# Positive_Pwr.net
KiCad netlist of a schematic drawn in Altium Designer
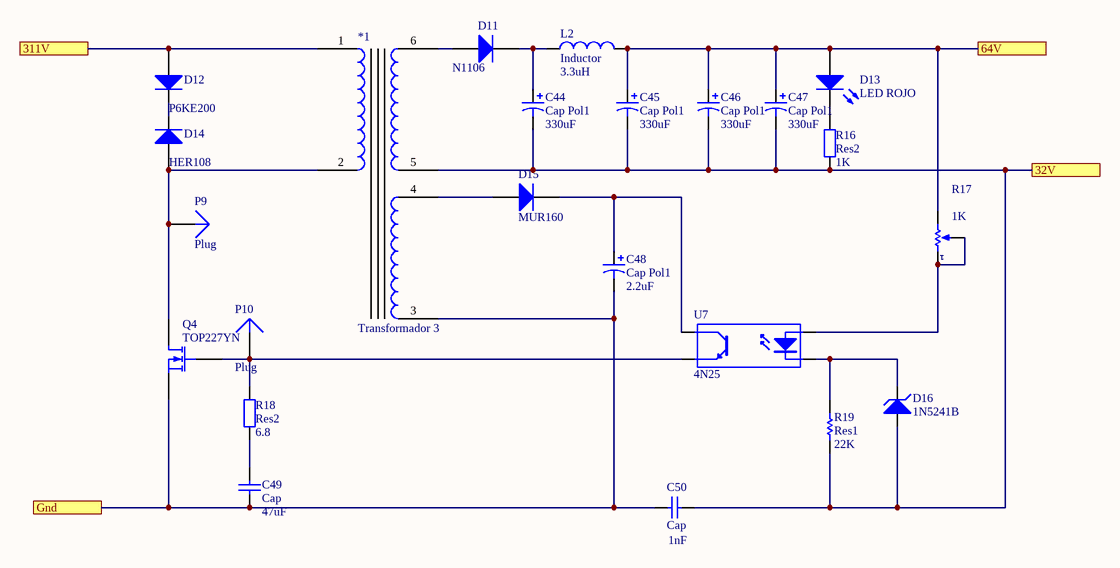
[diagram p0: Positive Pwr.SchDoc]

(export (version "E")
  (design (tool "Eeschema 10.0.6"))
  (components
    (comp (ref "*1")
      (value "Transformador 3")
      (footprint "Transformador_flyback - duplicate")
      (libsource (lib "Userlib") (part "Transformador 3"))
    )
    (comp (ref "C44")
      (value "Cap Pol1")
      (footprint "CAPR D500 H1200 R200 mil")
      (description "Polarized Capacitor (Radial)")
      (fields (field (name "ALTIUM_VALUE") "330uF") (field (name "PUBLISHER") "Altium Limited"))
      (libsource (lib "Miscellaneous Devices") (part "Cap Pol1"))
    )
    (comp (ref "C45")
      (value "Cap Pol1")
      (footprint "CAPR D500 H1200 R200 mil")
      (description "Polarized Capacitor (Radial)")
      (fields (field (name "ALTIUM_VALUE") "330uF") (field (name "PUBLISHER") "Altium Limited"))
      (libsource (lib "Miscellaneous Devices") (part "Cap Pol1"))
    )
    (comp (ref "C46")
      (value "Cap Pol1")
      (footprint "CAPR D500 H1200 R200 mil")
      (description "Polarized Capacitor (Radial)")
      (fields (field (name "ALTIUM_VALUE") "330uF") (field (name "PUBLISHER") "Altium Limited"))
      (libsource (lib "Miscellaneous Devices") (part "Cap Pol1"))
    )
    (comp (ref "C47")
      (value "Cap Pol1")
      (footprint "CAPR D500 H1200 R200 mil")
      (description "Polarized Capacitor (Radial)")
      (fields (field (name "ALTIUM_VALUE") "330uF") (field (name "PUBLISHER") "Altium Limited"))
      (libsource (lib "Miscellaneous Devices") (part "Cap Pol1"))
    )
    (comp (ref "C48")
      (value "Cap Pol1")
      (footprint "CAPR D200 H450 R100 mil")
      (description "Polarized Capacitor (Radial)")
      (fields (field (name "ALTIUM_VALUE") "2.2uF") (field (name "PUBLISHER") "Altium Limited"))
      (libsource (lib "Miscellaneous Devices") (part "Cap Pol1"))
    )
    (comp (ref "C49")
      (value "Cap")
      (footprint "CAPR D250 H450 R100 mil")
      (description "Capacitor")
      (fields (field (name "ALTIUM_VALUE") "47uF") (field (name "PUBLISHER") "Altium Limited"))
      (libsource (lib "Miscellaneous Devices") (part "Cap"))
    )
    (comp (ref "C50")
      (value "Cap")
      (footprint "RAD-0.2")
      (description "Capacitor")
      (fields (field (name "ALTIUM_VALUE") "1nF") (field (name "PUBLISHER") "Altium Limited"))
      (libsource (lib "Miscellaneous Devices") (part "Cap"))
    )
    (comp (ref "D11")
      (value "N1106")
      (footprint "TO-220_A")
      (description "High Conductance Fast Diode")
      (fields (field (name "PUBLISHER") "Altium Limited"))
      (libsource (lib "") (part "Diode 1N4148_1"))
    )
    (comp (ref "D12")
      (value "P6KE200")
      (footprint "DO-15")
      (description "High Conductance Fast Diode")
      (fields (field (name "PUBLISHER") "Altium Limited"))
      (libsource (lib "Miscellaneous Devices") (part "Diode 1N4148"))
    )
    (comp (ref "D13")
      (value "LED ROJO")
      (footprint "Led 5mm ROJO")
      (description "Typical INFRARED GaAs LED")
      (fields (field (name "PUBLISHER") "Altium Limited"))
      (libsource (lib "Miscellaneous Devices") (part "LED0"))
    )
    (comp (ref "D14")
      (value "HER108")
      (footprint "DO-41")
      (description "High Conductance Fast Diode")
      (fields (field (name "PUBLISHER") "Altium Limited"))
      (libsource (lib "Miscellaneous Devices") (part "Diode 1N4148"))
    )
    (comp (ref "D15")
      (value "MUR160")
      (footprint "DO-41")
      (description "High Conductance Fast Diode")
      (fields (field (name "PUBLISHER") "Altium Limited"))
      (libsource (lib "Miscellaneous Devices") (part "Diode 1N4148"))
    )
    (comp (ref "D16")
      (value "Diodo Zener")
      (footprint "DO-41")
      (fields (field (name "VALOR") "1N5241B"))
      (libsource (lib "RUF-Dispositivos-Grales") (part "Diodo Zener"))
    )
    (comp (ref "L2")
      (value "Inductor")
      (footprint "Bobina 1.5*3")
      (fields (field (name "ALTIUM_VALUE") "3.3uH") (field (name "PUBLISHER") "Altium Limited"))
      (libsource (lib "Miscellaneous Devices") (part "Inductor"))
    )
    (comp (ref "P9")
      (value "Plug")
      (footprint "PIN1")
      (fields (field (name "PUBLISHER") "Altium Limited"))
      (libsource (lib "Miscellaneous Connectors") (part "Plug"))
    )
    (comp (ref "P10")
      (value "Plug")
      (footprint "PIN1")
      (fields (field (name "PUBLISHER") "Altium Limited"))
      (libsource (lib "Miscellaneous Connectors") (part "Plug"))
    )
    (comp (ref "Q4")
      (value "TOP227YN")
      (footprint "TO-220AB")
      (description "N-Channel MOSFET")
      (fields (field (name "PUBLISHER") "Altium Limited"))
      (libsource (lib "Miscellaneous Devices") (part "MOSFET-N"))
    )
    (comp (ref "R16")
      (value "Res2")
      (footprint "1206 resistor")
      (description "Resistor")
      (fields (field (name "ALTIUM_VALUE") "1K") (field (name "PUBLISHER") "Altium Limited"))
      (libsource (lib "Miscellaneous Devices") (part "Res2"))
    )
    (comp (ref "R17")
      (value "Trimpot")
      (footprint "Trimpot Horizontal")
      (description "Preset")
      (fields (field (name "VALOR") "1K"))
      (libsource (lib "RUF-Dispositivos-Grales") (part "Trimpot"))
    )
    (comp (ref "R18")
      (value "Res2")
      (footprint "1206 resistor")
      (description "Resistor")
      (fields (field (name "ALTIUM_VALUE") "6.8") (field (name "PUBLISHER") "Altium Limited"))
      (libsource (lib "Miscellaneous Devices") (part "Res2"))
    )
    (comp (ref "R19")
      (value "Res1")
      (footprint "1206 resistor")
      (description "Resistor")
      (fields (field (name "ALTIUM_VALUE") "22K") (field (name "PUBLISHER") "Altium Limited"))
      (libsource (lib "Miscellaneous Devices") (part "Res1"))
    )
    (comp (ref "U7")
      (value "4N25")
      (footprint "DIP-4")
      (description "4-Pin Phototransistor Optocoupler")
      (fields (field (name "PUBLISHER") "Altium Limited"))
      (libsource (lib "Miscellaneous Devices") (part "Optoisolator1"))
    )
  )
  (nets
    (net (code "1") (name "/32V") (class "Default")
      (node (ref "*1") (pin "5") (pinfunction "L_5") (pintype "passive"))
      (node (ref "C44") (pin "2") (pinfunction "2_2") (pintype "passive"))
      (node (ref "C45") (pin "2") (pinfunction "2_2") (pintype "passive"))
      (node (ref "C46") (pin "2") (pinfunction "2_2") (pintype "passive"))
      (node (ref "C47") (pin "2") (pinfunction "2_2") (pintype "passive"))
      (node (ref "C50") (pin "2") (pinfunction "2_2") (pintype "passive"))
      (node (ref "D16") (pin "1") (pinfunction "A_1") (pintype "passive"))
      (node (ref "R16") (pin "1") (pinfunction "1_1") (pintype "passive"))
      (node (ref "R19") (pin "1") (pinfunction "1_1") (pintype "passive"))
    )
    (net (code "2") (name "/64V") (class "Default")
      (node (ref "C45") (pin "1") (pinfunction "1_1") (pintype "passive"))
      (node (ref "C46") (pin "1") (pinfunction "1_1") (pintype "passive"))
      (node (ref "C47") (pin "1") (pinfunction "1_1") (pintype "passive"))
      (node (ref "D13") (pin "1") (pinfunction "A_1") (pintype "passive"))
      (node (ref "L2") (pin "2") (pinfunction "2_2") (pintype "passive"))
      (node (ref "R17") (pin "2") (pinfunction "BOT_2") (pintype "passive"))
    )
    (net (code "3") (name "/311V") (class "Default")
      (node (ref "*1") (pin "1") (pinfunction "L_1") (pintype "passive"))
      (node (ref "D12") (pin "1") (pinfunction "A_1") (pintype "passive"))
    )
    (net (code "4") (name "/Gnd") (class "Default")
      (node (ref "*1") (pin "3") (pinfunction "L_3") (pintype "passive"))
      (node (ref "C48") (pin "2") (pinfunction "2_2") (pintype "passive"))
      (node (ref "C49") (pin "1") (pinfunction "1_1") (pintype "passive"))
      (node (ref "C50") (pin "1") (pinfunction "1_1") (pintype "passive"))
      (node (ref "Q4") (pin "2") (pinfunction "S_2") (pintype "passive"))
    )
    (net (code "5") (name "Net-(C49-Pad2)") (class "Default")
      (node (ref "C49") (pin "2") (pinfunction "2_2") (pintype "passive"))
      (node (ref "R18") (pin "1") (pinfunction "1_1") (pintype "passive"))
    )
    (net (code "6") (name "Net-(D11-A)") (class "Default")
      (node (ref "*1") (pin "6") (pinfunction "L_6") (pintype "passive"))
      (node (ref "D11") (pin "3") (pinfunction "A_3") (pintype "passive"))
    )
    (net (code "7") (name "Net-(D11-K)") (class "Default")
      (node (ref "C44") (pin "1") (pinfunction "1_1") (pintype "passive"))
      (node (ref "D11") (pin "1") (pinfunction "K_1") (pintype "passive"))
      (node (ref "L2") (pin "1") (pinfunction "1_1") (pintype "passive"))
    )
    (net (code "8") (name "Net-(D12-K)") (class "Default")
      (node (ref "D12") (pin "2") (pinfunction "K_2") (pintype "passive"))
      (node (ref "D14") (pin "2") (pinfunction "K_2") (pintype "passive"))
    )
    (net (code "9") (name "Net-(D13-K)") (class "Default")
      (node (ref "D13") (pin "2") (pinfunction "K_2") (pintype "passive"))
      (node (ref "R16") (pin "2") (pinfunction "2_2") (pintype "passive"))
    )
    (net (code "10") (name "Net-(D14-A)") (class "Default")
      (node (ref "*1") (pin "2") (pinfunction "L_2") (pintype "passive"))
      (node (ref "D14") (pin "1") (pinfunction "A_1") (pintype "passive"))
      (node (ref "P9") (pin "1") (pinfunction "1_1") (pintype "passive"))
      (node (ref "Q4") (pin "3") (pinfunction "D_3") (pintype "passive"))
    )
    (net (code "11") (name "Net-(D15-A)") (class "Default")
      (node (ref "*1") (pin "4") (pinfunction "L_4") (pintype "passive"))
      (node (ref "D15") (pin "1") (pinfunction "A_1") (pintype "passive"))
    )
    (net (code "12") (name "Net-(D15-K)") (class "Default")
      (node (ref "C48") (pin "1") (pinfunction "1_1") (pintype "passive"))
      (node (ref "D15") (pin "2") (pinfunction "K_2") (pintype "passive"))
      (node (ref "U7") (pin "4") (pinfunction "C_4") (pintype "passive"))
    )
    (net (code "13") (name "Net-(D16-K)") (class "Default")
      (node (ref "D16") (pin "2") (pinfunction "K_2") (pintype "passive"))
      (node (ref "R19") (pin "2") (pinfunction "2_2") (pintype "passive"))
      (node (ref "U7") (pin "2") (pinfunction "K_2") (pintype "passive"))
    )
    (net (code "14") (name "Net-(Q4-G)") (class "Default")
      (node (ref "P10") (pin "1") (pinfunction "1_1") (pintype "passive"))
      (node (ref "Q4") (pin "1") (pinfunction "G_1") (pintype "passive"))
      (node (ref "R18") (pin "2") (pinfunction "2_2") (pintype "passive"))
      (node (ref "U7") (pin "3") (pinfunction "E_3") (pintype "passive"))
    )
    (net (code "15") (name "Net-(R17-TAP)") (class "Default")
      (node (ref "R17") (pin "1") (pinfunction "TOP_1") (pintype "passive"))
      (node (ref "R17") (pin "3") (pinfunction "TAP_3") (pintype "passive"))
      (node (ref "U7") (pin "1") (pinfunction "A_1") (pintype "passive"))
    )
  )
)
